# AE-AQM0802-board.net
KiCad netlist of a schematic drawn in EAGLE
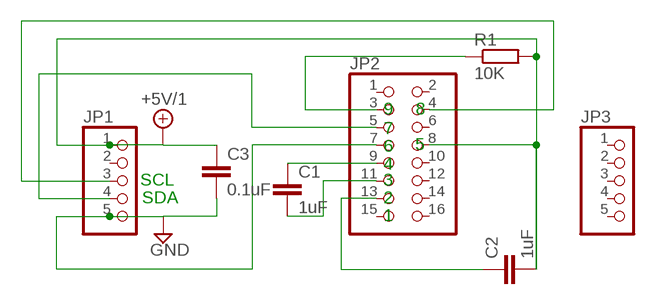
[diagram p0: schematic, sheet 1]

(export (version "E")
  (design (tool "Eeschema 10.0.6"))
  (components
    (comp (ref "C1")
      (value "1uF")
      (footprint "eagle-import:C0504")
      (libsource (lib "eagle-import") (part "C-EUC0504"))
    )
    (comp (ref "C2")
      (value "1uF")
      (footprint "eagle-import:C0504")
      (libsource (lib "eagle-import") (part "C-EUC0504"))
    )
    (comp (ref "C3")
      (value "0.1uF")
      (footprint "eagle-import:C0504")
      (libsource (lib "eagle-import") (part "C-EUC0504"))
    )
    (comp (ref "JP1")
      (value "PINHD-1X5")
      (footprint "eagle-import:1X05")
      (libsource (lib "eagle-import") (part "PINHD-1X5"))
    )
    (comp (ref "JP2")
      (value "PINHD-2X8")
      (footprint "eagle-import:2X08")
      (libsource (lib "eagle-import") (part "PINHD-2X8"))
    )
    (comp (ref "JP3")
      (value "PINHD-1X5")
      (footprint "eagle-import:1X05")
      (libsource (lib "eagle-import") (part "PINHD-1X5"))
    )
    (comp (ref "R1")
      (value "10K")
      (footprint "eagle-import:M2012")
      (libsource (lib "eagle-import") (part "R-EU_M2012"))
    )
  )
  (nets
    (net (code "1") (name "+5V{slash}1") (class "Default")
      (node (ref "C2") (pin "2") (pinfunction "2_2") (pintype "passive"))
      (node (ref "C3") (pin "1") (pinfunction "1_1") (pintype "passive"))
      (node (ref "JP1") (pin "1") (pinfunction "1_1") (pintype "passive"))
      (node (ref "JP2") (pin "8") (pinfunction "8_8") (pintype "passive"))
      (node (ref "R1") (pin "2") (pinfunction "2_2") (pintype "passive"))
    )
    (net (code "2") (name "GND") (class "Default")
      (node (ref "C3") (pin "2") (pinfunction "2_2") (pintype "passive"))
      (node (ref "JP1") (pin "5") (pinfunction "5_5") (pintype "passive"))
      (node (ref "JP2") (pin "7") (pinfunction "7_7") (pintype "passive"))
    )
    (net (code "3") (name "Net-(C1-Pad1)") (class "Default")
      (node (ref "C1") (pin "1") (pinfunction "1_1") (pintype "passive"))
      (node (ref "JP2") (pin "9") (pinfunction "9_9") (pintype "passive"))
    )
    (net (code "4") (name "Net-(C1-Pad2)") (class "Default")
      (node (ref "C1") (pin "2") (pinfunction "2_2") (pintype "passive"))
      (node (ref "JP2") (pin "11") (pinfunction "11_11") (pintype "passive"))
    )
    (net (code "5") (name "Net-(C2-Pad1)") (class "Default")
      (node (ref "C2") (pin "1") (pinfunction "1_1") (pintype "passive"))
      (node (ref "JP2") (pin "13") (pinfunction "13_13") (pintype "passive"))
    )
    (net (code "6") (name "Net-(JP1-Pad3)") (class "Default")
      (node (ref "JP1") (pin "3") (pinfunction "3_3") (pintype "passive"))
      (node (ref "JP2") (pin "4") (pinfunction "4_4") (pintype "passive"))
    )
    (net (code "7") (name "Net-(JP1-Pad4)") (class "Default")
      (node (ref "JP1") (pin "4") (pinfunction "4_4") (pintype "passive"))
      (node (ref "JP2") (pin "5") (pinfunction "5_5") (pintype "passive"))
    )
    (net (code "8") (name "Net-(JP2-Pad3)") (class "Default")
      (node (ref "JP2") (pin "3") (pinfunction "3_3") (pintype "passive"))
      (node (ref "R1") (pin "1") (pinfunction "1_1") (pintype "passive"))
    )
    (net (code "9") (name "unconnected-(JP1-Pad2)") (class "Default")
      (node (ref "JP1") (pin "2") (pinfunction "2_2") (pintype "passive"))
    )
    (net (code "10") (name "unconnected-(JP2-Pad1)") (class "Default")
      (node (ref "JP2") (pin "1") (pinfunction "1_1") (pintype "passive"))
    )
    (net (code "11") (name "unconnected-(JP2-Pad2)") (class "Default")
      (node (ref "JP2") (pin "2") (pinfunction "2_2") (pintype "passive"))
    )
    (net (code "12") (name "unconnected-(JP2-Pad6)") (class "Default")
      (node (ref "JP2") (pin "6") (pinfunction "6_6") (pintype "passive"))
    )
    (net (code "13") (name "unconnected-(JP2-Pad10)") (class "Default")
      (node (ref "JP2") (pin "10") (pinfunction "10_10") (pintype "passive"))
    )
    (net (code "14") (name "unconnected-(JP2-Pad12)") (class "Default")
      (node (ref "JP2") (pin "12") (pinfunction "12_12") (pintype "passive"))
    )
    (net (code "15") (name "unconnected-(JP2-Pad14)") (class "Default")
      (node (ref "JP2") (pin "14") (pinfunction "14_14") (pintype "passive"))
    )
    (net (code "16") (name "unconnected-(JP2-Pad15)") (class "Default")
      (node (ref "JP2") (pin "15") (pinfunction "15_15") (pintype "passive"))
    )
    (net (code "17") (name "unconnected-(JP2-Pad16)") (class "Default")
      (node (ref "JP2") (pin "16") (pinfunction "16_16") (pintype "passive"))
    )
    (net (code "18") (name "unconnected-(JP3-Pad1)") (class "Default")
      (node (ref "JP3") (pin "1") (pinfunction "1_1") (pintype "passive"))
    )
    (net (code "19") (name "unconnected-(JP3-Pad2)") (class "Default")
      (node (ref "JP3") (pin "2") (pinfunction "2_2") (pintype "passive"))
    )
    (net (code "20") (name "unconnected-(JP3-Pad3)") (class "Default")
      (node (ref "JP3") (pin "3") (pinfunction "3_3") (pintype "passive"))
    )
    (net (code "21") (name "unconnected-(JP3-Pad4)") (class "Default")
      (node (ref "JP3") (pin "4") (pinfunction "4_4") (pintype "passive"))
    )
    (net (code "22") (name "unconnected-(JP3-Pad5)") (class "Default")
      (node (ref "JP3") (pin "5") (pinfunction "5_5") (pintype "passive"))
    )
  )
)
